# MegaPlay.net
KiCad netlist of a schematic drawn in EAGLE
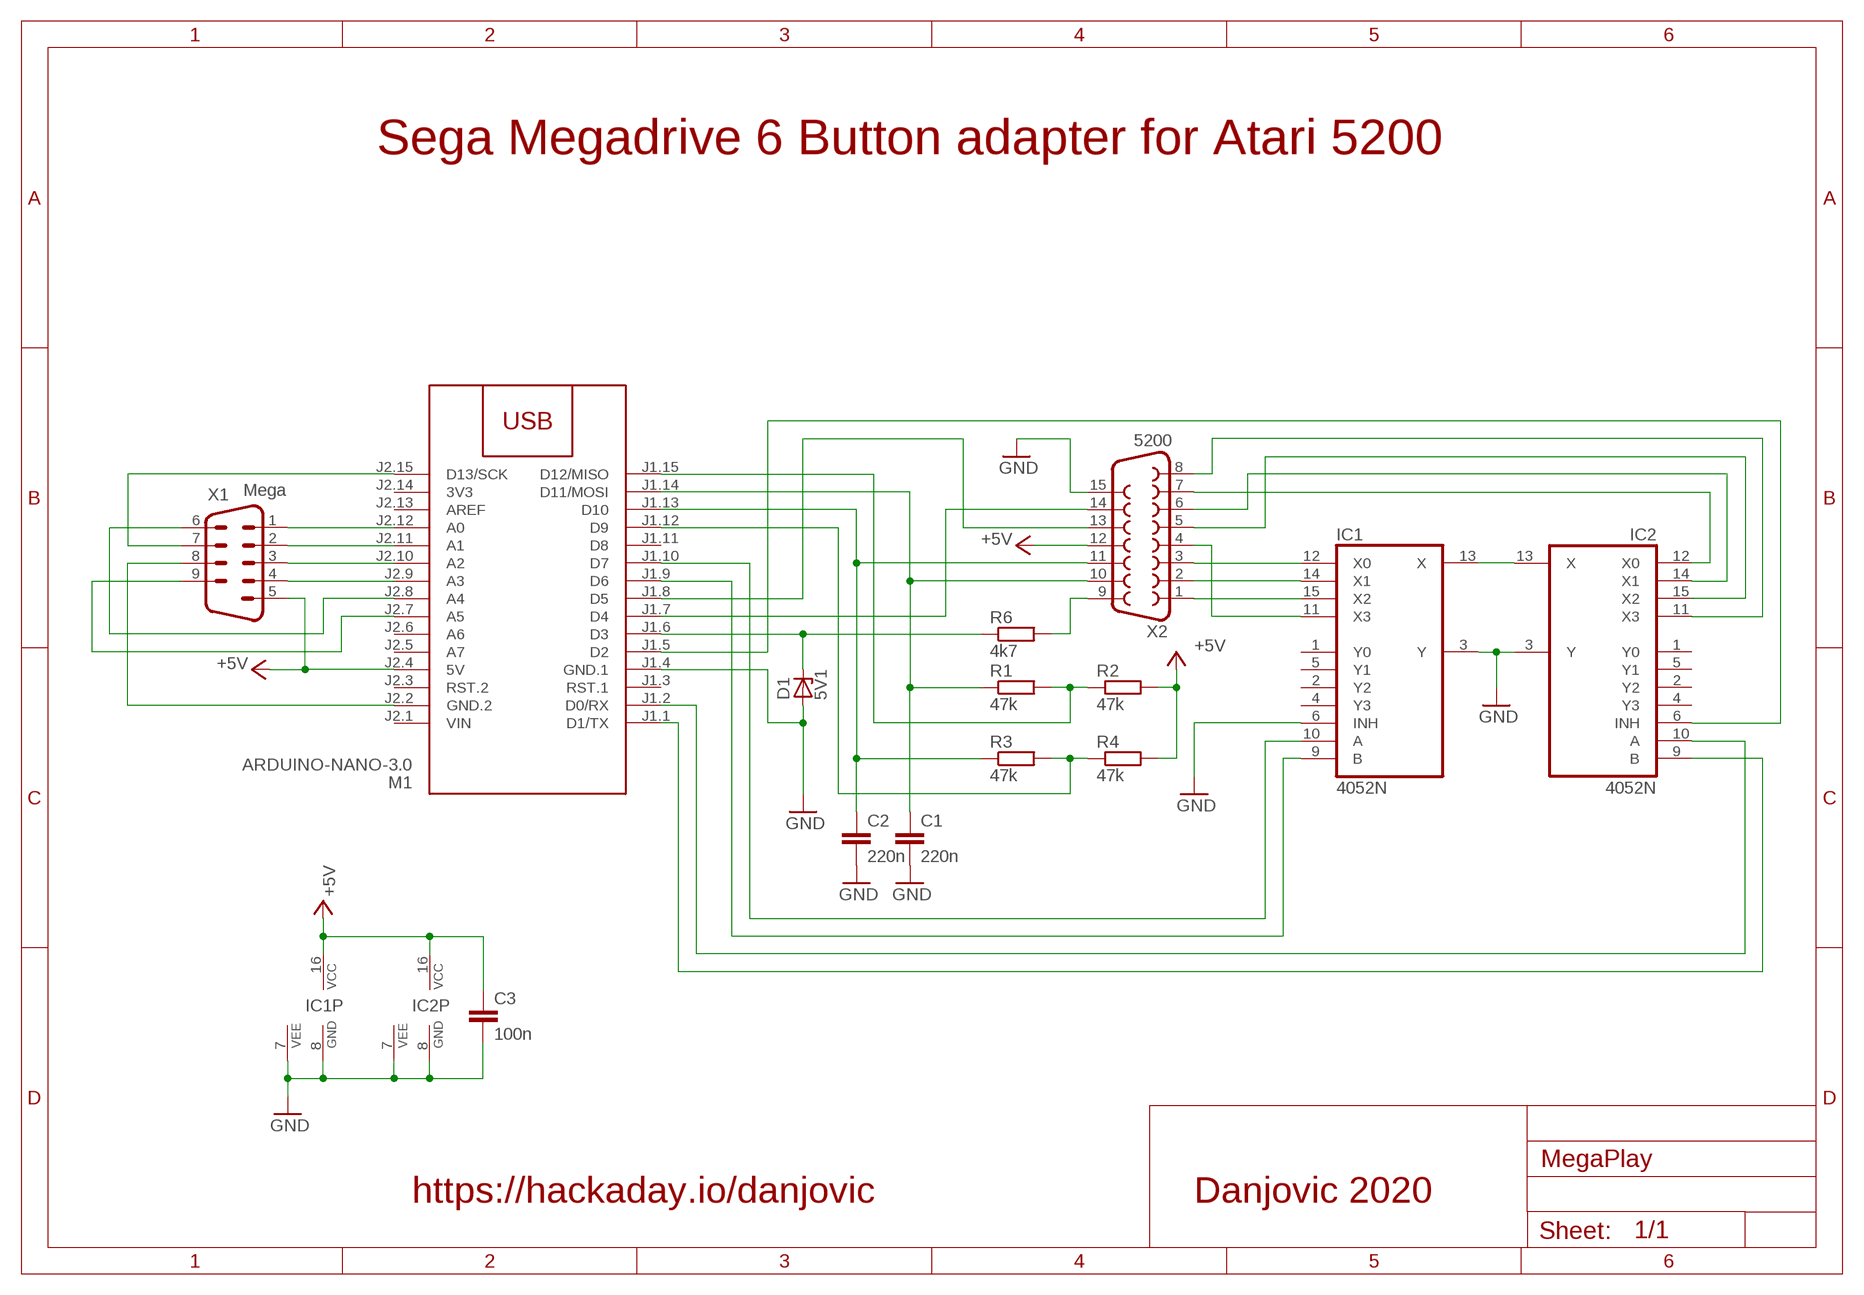
[diagram p0: schematic, sheet 1]

(export (version "E")
  (design (tool "Eeschema 10.0.6"))
  (components
    (comp (ref "C1")
      (value "220n")
      (footprint "eagle-import:C050-025X075")
      (libsource (lib "eagle-import") (part "C-EU050-025X075"))
    )
    (comp (ref "C2")
      (value "220n")
      (footprint "eagle-import:C050-025X075")
      (libsource (lib "eagle-import") (part "C-EU050-025X075"))
    )
    (comp (ref "C3")
      (value "100n")
      (footprint "eagle-import:C050-024X044")
      (libsource (lib "eagle-import") (part "C-EU050-024X044"))
    )
    (comp (ref "D1")
      (value "5V1")
      (footprint "eagle-import:ZDIO-7.5")
      (libsource (lib "eagle-import") (part "ZENER-DIODEZD-7.5"))
    )
    (comp (ref "IC1")
      (value "4052N")
      (footprint "eagle-import:DIL16")
      (libsource (lib "eagle-import") (part "4052N"))
    )
    (comp (ref "IC2")
      (value "4052N")
      (footprint "eagle-import:DIL16")
      (libsource (lib "eagle-import") (part "4052N"))
    )
    (comp (ref "M1")
      (value "ARDUINO-NANO-3.0")
      (footprint "eagle-import:ARDUINO-NANO-3.0")
      (libsource (lib "eagle-import") (part "ARDUINO-NANO-3.0"))
    )
    (comp (ref "R1")
      (value "47k")
      (footprint "eagle-import:0204_7")
      (libsource (lib "eagle-import") (part "R-EU_0204/7"))
    )
    (comp (ref "R2")
      (value "47k")
      (footprint "eagle-import:0204_7")
      (libsource (lib "eagle-import") (part "R-EU_0204/7"))
    )
    (comp (ref "R3")
      (value "47k")
      (footprint "eagle-import:0204_7")
      (libsource (lib "eagle-import") (part "R-EU_0204/7"))
    )
    (comp (ref "R4")
      (value "47k")
      (footprint "eagle-import:0204_7")
      (libsource (lib "eagle-import") (part "R-EU_0204/7"))
    )
    (comp (ref "R6")
      (value "4k7")
      (footprint "eagle-import:0204_7")
      (libsource (lib "eagle-import") (part "R-EU_0204/7"))
    )
    (comp (ref "X1")
      (value "Mega")
      (footprint "eagle-import:M09D")
      (libsource (lib "eagle-import") (part "M09D"))
    )
    (comp (ref "X2")
      (value "5200")
      (footprint "eagle-import:F15D")
      (libsource (lib "eagle-import") (part "F15D"))
    )
  )
  (nets
    (net (code "1") (name "+5V") (class "Default")
      (node (ref "C3") (pin "1") (pinfunction "1_1") (pintype "passive"))
      (node (ref "IC1") (pin "16") (pinfunction "VCC_16") (pintype "power_in"))
      (node (ref "IC2") (pin "16") (pinfunction "VCC_16") (pintype "power_in"))
      (node (ref "M1") (pin "J2.4") (pinfunction "5V_J2.4") (pintype "power_in"))
      (node (ref "R2") (pin "2") (pinfunction "2_2") (pintype "passive"))
      (node (ref "R4") (pin "2") (pinfunction "2_2") (pintype "passive"))
      (node (ref "X1") (pin "5") (pinfunction "5_5") (pintype "passive"))
      (node (ref "X2") (pin "12") (pinfunction "12_12") (pintype "passive"))
    )
    (net (code "2") (name "/3V3") (class "Default")
      (node (ref "M1") (pin "J2.14") (pinfunction "3V3_J2.14") (pintype "power_in"))
    )
    (net (code "3") (name "/VIN") (class "Default")
      (node (ref "M1") (pin "J2.1") (pinfunction "VIN_J2.1") (pintype "power_in"))
    )
    (net (code "4") (name "GND") (class "Default")
      (node (ref "C1") (pin "2") (pinfunction "2_2") (pintype "passive"))
      (node (ref "C2") (pin "2") (pinfunction "2_2") (pintype "passive"))
      (node (ref "C3") (pin "2") (pinfunction "2_2") (pintype "passive"))
      (node (ref "D1") (pin "A") (pinfunction "A_A") (pintype "passive"))
      (node (ref "IC1") (pin "3") (pinfunction "Y_3") (pintype "bidirectional"))
      (node (ref "IC1") (pin "6") (pinfunction "INH_6") (pintype "input"))
      (node (ref "IC1") (pin "7") (pinfunction "VEE_7") (pintype "power_in"))
      (node (ref "IC1") (pin "8") (pinfunction "GND_8") (pintype "power_in"))
      (node (ref "IC2") (pin "3") (pinfunction "Y_3") (pintype "bidirectional"))
      (node (ref "IC2") (pin "7") (pinfunction "VEE_7") (pintype "power_in"))
      (node (ref "IC2") (pin "8") (pinfunction "GND_8") (pintype "power_in"))
      (node (ref "M1") (pin "J1.4") (pinfunction "GND.1_J1.4") (pintype "power_in"))
      (node (ref "X2") (pin "15") (pinfunction "15_15") (pintype "passive"))
    )
    (net (code "5") (name "Net-(IC1A-A)") (class "Default")
      (node (ref "IC1") (pin "10") (pinfunction "A_10") (pintype "input"))
      (node (ref "M1") (pin "J1.10") (pinfunction "D7_J1.10") (pintype "bidirectional"))
    )
    (net (code "6") (name "Net-(IC1A-B)") (class "Default")
      (node (ref "IC1") (pin "9") (pinfunction "B_9") (pintype "input"))
      (node (ref "M1") (pin "J1.9") (pinfunction "D6_J1.9") (pintype "bidirectional"))
    )
    (net (code "7") (name "Net-(IC1A-X)") (class "Default")
      (node (ref "IC1") (pin "13") (pinfunction "X_13") (pintype "bidirectional"))
      (node (ref "IC2") (pin "13") (pinfunction "X_13") (pintype "bidirectional"))
    )
    (net (code "8") (name "Net-(IC1A-X0)") (class "Default")
      (node (ref "IC1") (pin "12") (pinfunction "X0_12") (pintype "bidirectional"))
      (node (ref "X2") (pin "3") (pinfunction "3_3") (pintype "passive"))
    )
    (net (code "9") (name "Net-(IC1A-X1)") (class "Default")
      (node (ref "IC1") (pin "14") (pinfunction "X1_14") (pintype "bidirectional"))
      (node (ref "X2") (pin "2") (pinfunction "2_2") (pintype "passive"))
    )
    (net (code "10") (name "Net-(IC1A-X2)") (class "Default")
      (node (ref "IC1") (pin "15") (pinfunction "X2_15") (pintype "bidirectional"))
      (node (ref "X2") (pin "1") (pinfunction "1_1") (pintype "passive"))
    )
    (net (code "11") (name "Net-(IC1A-X3)") (class "Default")
      (node (ref "IC1") (pin "11") (pinfunction "X3_11") (pintype "bidirectional"))
      (node (ref "X2") (pin "4") (pinfunction "4_4") (pintype "passive"))
    )
    (net (code "12") (name "Net-(IC2A-A)") (class "Default")
      (node (ref "IC2") (pin "10") (pinfunction "A_10") (pintype "input"))
      (node (ref "M1") (pin "J1.2") (pinfunction "D0/RX_J1.2") (pintype "bidirectional"))
    )
    (net (code "13") (name "Net-(IC2A-B)") (class "Default")
      (node (ref "IC2") (pin "9") (pinfunction "B_9") (pintype "input"))
      (node (ref "M1") (pin "J1.1") (pinfunction "D1/TX_J1.1") (pintype "bidirectional"))
    )
    (net (code "14") (name "Net-(IC2A-INH)") (class "Default")
      (node (ref "IC2") (pin "6") (pinfunction "INH_6") (pintype "input"))
      (node (ref "M1") (pin "J1.5") (pinfunction "D2_J1.5") (pintype "bidirectional"))
    )
    (net (code "15") (name "Net-(IC2A-X0)") (class "Default")
      (node (ref "IC2") (pin "12") (pinfunction "X0_12") (pintype "bidirectional"))
      (node (ref "X2") (pin "7") (pinfunction "7_7") (pintype "passive"))
    )
    (net (code "16") (name "Net-(IC2A-X1)") (class "Default")
      (node (ref "IC2") (pin "14") (pinfunction "X1_14") (pintype "bidirectional"))
      (node (ref "X2") (pin "6") (pinfunction "6_6") (pintype "passive"))
    )
    (net (code "17") (name "Net-(IC2A-X2)") (class "Default")
      (node (ref "IC2") (pin "15") (pinfunction "X2_15") (pintype "bidirectional"))
      (node (ref "X2") (pin "5") (pinfunction "5_5") (pintype "passive"))
    )
    (net (code "18") (name "Net-(IC2A-X3)") (class "Default")
      (node (ref "IC2") (pin "11") (pinfunction "X3_11") (pintype "bidirectional"))
      (node (ref "X2") (pin "8") (pinfunction "8_8") (pintype "passive"))
    )
    (net (code "19") (name "Net-(M1-A0)") (class "Default")
      (node (ref "M1") (pin "J2.12") (pinfunction "A0_J2.12") (pintype "bidirectional"))
      (node (ref "X1") (pin "1") (pinfunction "1_1") (pintype "passive"))
    )
    (net (code "20") (name "Net-(M1-A1)") (class "Default")
      (node (ref "M1") (pin "J2.11") (pinfunction "A1_J2.11") (pintype "bidirectional"))
      (node (ref "X1") (pin "2") (pinfunction "2_2") (pintype "passive"))
    )
    (net (code "21") (name "Net-(M1-A2)") (class "Default")
      (node (ref "M1") (pin "J2.10") (pinfunction "A2_J2.10") (pintype "bidirectional"))
      (node (ref "X1") (pin "3") (pinfunction "3_3") (pintype "passive"))
    )
    (net (code "22") (name "Net-(M1-A3)") (class "Default")
      (node (ref "M1") (pin "J2.9") (pinfunction "A3_J2.9") (pintype "bidirectional"))
      (node (ref "X1") (pin "4") (pinfunction "4_4") (pintype "passive"))
    )
    (net (code "23") (name "Net-(M1-A4)") (class "Default")
      (node (ref "M1") (pin "J2.8") (pinfunction "A4_J2.8") (pintype "bidirectional"))
      (node (ref "X1") (pin "6") (pinfunction "6_6") (pintype "passive"))
    )
    (net (code "24") (name "Net-(M1-A5)") (class "Default")
      (node (ref "M1") (pin "J2.7") (pinfunction "A5_J2.7") (pintype "bidirectional"))
      (node (ref "X1") (pin "9") (pinfunction "9_9") (pintype "passive"))
    )
    (net (code "25") (name "Net-(M1-D3)") (class "Default")
      (node (ref "D1") (pin "C") (pinfunction "C_C") (pintype "passive"))
      (node (ref "M1") (pin "J1.6") (pinfunction "D3_J1.6") (pintype "bidirectional"))
      (node (ref "R6") (pin "1") (pinfunction "1_1") (pintype "passive"))
    )
    (net (code "26") (name "Net-(M1-D4)") (class "Default")
      (node (ref "M1") (pin "J1.7") (pinfunction "D4_J1.7") (pintype "bidirectional"))
      (node (ref "X2") (pin "14") (pinfunction "14_14") (pintype "passive"))
    )
    (net (code "27") (name "Net-(M1-D5)") (class "Default")
      (node (ref "M1") (pin "J1.8") (pinfunction "D5_J1.8") (pintype "bidirectional"))
      (node (ref "X2") (pin "13") (pinfunction "13_13") (pintype "passive"))
    )
    (net (code "28") (name "Net-(M1-D9)") (class "Default")
      (node (ref "M1") (pin "J1.12") (pinfunction "D9_J1.12") (pintype "bidirectional"))
      (node (ref "R3") (pin "2") (pinfunction "2_2") (pintype "passive"))
      (node (ref "R4") (pin "1") (pinfunction "1_1") (pintype "passive"))
    )
    (net (code "29") (name "Net-(M1-D10)") (class "Default")
      (node (ref "C2") (pin "1") (pinfunction "1_1") (pintype "passive"))
      (node (ref "M1") (pin "J1.13") (pinfunction "D10_J1.13") (pintype "bidirectional"))
      (node (ref "R3") (pin "1") (pinfunction "1_1") (pintype "passive"))
      (node (ref "X2") (pin "11") (pinfunction "11_11") (pintype "passive"))
    )
    (net (code "30") (name "Net-(M1-D11{slash}MOSI)") (class "Default")
      (node (ref "C1") (pin "1") (pinfunction "1_1") (pintype "passive"))
      (node (ref "M1") (pin "J1.14") (pinfunction "D11/MOSI_J1.14") (pintype "bidirectional"))
      (node (ref "R1") (pin "1") (pinfunction "1_1") (pintype "passive"))
      (node (ref "X2") (pin "10") (pinfunction "10_10") (pintype "passive"))
    )
    (net (code "31") (name "Net-(M1-D12{slash}MISO)") (class "Default")
      (node (ref "M1") (pin "J1.15") (pinfunction "D12/MISO_J1.15") (pintype "bidirectional"))
      (node (ref "R1") (pin "2") (pinfunction "2_2") (pintype "passive"))
      (node (ref "R2") (pin "1") (pinfunction "1_1") (pintype "passive"))
    )
    (net (code "32") (name "Net-(M1-D13{slash}SCK)") (class "Default")
      (node (ref "M1") (pin "J2.15") (pinfunction "D13/SCK_J2.15") (pintype "bidirectional"))
      (node (ref "X1") (pin "7") (pinfunction "7_7") (pintype "passive"))
    )
    (net (code "33") (name "Net-(M1-GND.2)") (class "Default")
      (node (ref "M1") (pin "J2.2") (pinfunction "GND.2_J2.2") (pintype "power_in"))
      (node (ref "X1") (pin "8") (pinfunction "8_8") (pintype "passive"))
    )
    (net (code "34") (name "Net-(R6-Pad2)") (class "Default")
      (node (ref "R6") (pin "2") (pinfunction "2_2") (pintype "passive"))
      (node (ref "X2") (pin "9") (pinfunction "9_9") (pintype "passive"))
    )
    (net (code "35") (name "unconnected-(IC1A-Y0-Pad1)") (class "Default")
      (node (ref "IC1") (pin "1") (pinfunction "Y0_1") (pintype "bidirectional"))
    )
    (net (code "36") (name "unconnected-(IC1A-Y1-Pad5)") (class "Default")
      (node (ref "IC1") (pin "5") (pinfunction "Y1_5") (pintype "bidirectional"))
    )
    (net (code "37") (name "unconnected-(IC1A-Y2-Pad2)") (class "Default")
      (node (ref "IC1") (pin "2") (pinfunction "Y2_2") (pintype "bidirectional"))
    )
    (net (code "38") (name "unconnected-(IC1A-Y3-Pad4)") (class "Default")
      (node (ref "IC1") (pin "4") (pinfunction "Y3_4") (pintype "bidirectional"))
    )
    (net (code "39") (name "unconnected-(IC2A-Y0-Pad1)") (class "Default")
      (node (ref "IC2") (pin "1") (pinfunction "Y0_1") (pintype "bidirectional"))
    )
    (net (code "40") (name "unconnected-(IC2A-Y1-Pad5)") (class "Default")
      (node (ref "IC2") (pin "5") (pinfunction "Y1_5") (pintype "bidirectional"))
    )
    (net (code "41") (name "unconnected-(IC2A-Y2-Pad2)") (class "Default")
      (node (ref "IC2") (pin "2") (pinfunction "Y2_2") (pintype "bidirectional"))
    )
    (net (code "42") (name "unconnected-(IC2A-Y3-Pad4)") (class "Default")
      (node (ref "IC2") (pin "4") (pinfunction "Y3_4") (pintype "bidirectional"))
    )
    (net (code "43") (name "unconnected-(M1-A6-PadJ2.6)") (class "Default")
      (node (ref "M1") (pin "J2.6") (pinfunction "A6_J2.6") (pintype "bidirectional"))
    )
    (net (code "44") (name "unconnected-(M1-A7-PadJ2.5)") (class "Default")
      (node (ref "M1") (pin "J2.5") (pinfunction "A7_J2.5") (pintype "bidirectional"))
    )
    (net (code "45") (name "unconnected-(M1-AREF-PadJ2.13)") (class "Default")
      (node (ref "M1") (pin "J2.13") (pinfunction "AREF_J2.13") (pintype "bidirectional"))
    )
    (net (code "46") (name "unconnected-(M1-D8-PadJ1.11)") (class "Default")
      (node (ref "M1") (pin "J1.11") (pinfunction "D8_J1.11") (pintype "bidirectional"))
    )
    (net (code "47") (name "unconnected-(M1-RST.1-PadJ1.3)") (class "Default")
      (node (ref "M1") (pin "J1.3") (pinfunction "RST.1_J1.3") (pintype "bidirectional"))
    )
    (net (code "48") (name "unconnected-(M1-RST.2-PadJ2.3)") (class "Default")
      (node (ref "M1") (pin "J2.3") (pinfunction "RST.2_J2.3") (pintype "bidirectional"))
    )
  )
)
